# LED_Matrix_3_2.net
KiCad netlist of a schematic drawn in EAGLE
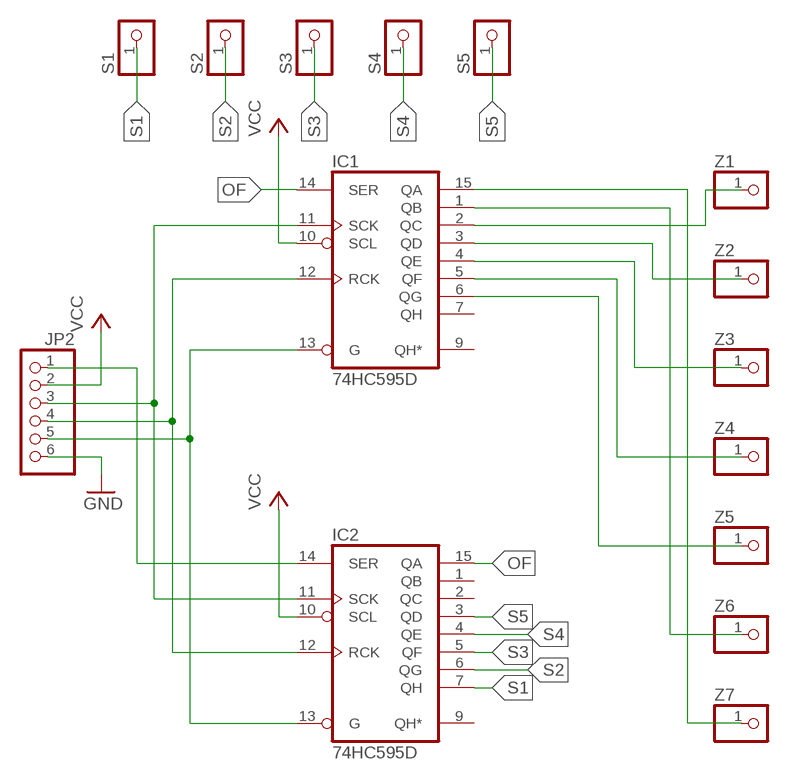
[diagram p0: schematic, sheet 1]

(export (version "E")
  (design (tool "Eeschema 10.0.6"))
  (components
    (comp (ref "IC1")
      (value "74HC595D")
      (footprint "eagle-import:SO16")
      (libsource (lib "eagle-import") (part "74595DHC"))
    )
    (comp (ref "IC2")
      (value "74HC595D")
      (footprint "eagle-import:SO16")
      (libsource (lib "eagle-import") (part "74595DHC"))
    )
    (comp (ref "JP2")
      (value "PINHD-1X6")
      (footprint "eagle-import:1X06")
      (libsource (lib "eagle-import") (part "PINHD-1X6"))
    )
    (comp (ref "S1")
      (value "PINHD-1X1")
      (footprint "eagle-import:1X01")
      (libsource (lib "eagle-import") (part "PINHD-1X1"))
    )
    (comp (ref "S2")
      (value "PINHD-1X1")
      (footprint "eagle-import:1X01")
      (libsource (lib "eagle-import") (part "PINHD-1X1"))
    )
    (comp (ref "S3")
      (value "PINHD-1X1")
      (footprint "eagle-import:1X01")
      (libsource (lib "eagle-import") (part "PINHD-1X1"))
    )
    (comp (ref "S4")
      (value "PINHD-1X1")
      (footprint "eagle-import:1X01")
      (libsource (lib "eagle-import") (part "PINHD-1X1"))
    )
    (comp (ref "S5")
      (value "PINHD-1X1")
      (footprint "eagle-import:1X01")
      (libsource (lib "eagle-import") (part "PINHD-1X1"))
    )
    (comp (ref "Z1")
      (value "PINHD-1X1")
      (footprint "eagle-import:1X01")
      (libsource (lib "eagle-import") (part "PINHD-1X1"))
    )
    (comp (ref "Z2")
      (value "PINHD-1X1")
      (footprint "eagle-import:1X01")
      (libsource (lib "eagle-import") (part "PINHD-1X1"))
    )
    (comp (ref "Z3")
      (value "PINHD-1X1")
      (footprint "eagle-import:1X01")
      (libsource (lib "eagle-import") (part "PINHD-1X1"))
    )
    (comp (ref "Z4")
      (value "PINHD-1X1")
      (footprint "eagle-import:1X01")
      (libsource (lib "eagle-import") (part "PINHD-1X1"))
    )
    (comp (ref "Z5")
      (value "PINHD-1X1")
      (footprint "eagle-import:1X01")
      (libsource (lib "eagle-import") (part "PINHD-1X1"))
    )
    (comp (ref "Z6")
      (value "PINHD-1X1")
      (footprint "eagle-import:1X01")
      (libsource (lib "eagle-import") (part "PINHD-1X1"))
    )
    (comp (ref "Z7")
      (value "PINHD-1X1")
      (footprint "eagle-import:1X01")
      (libsource (lib "eagle-import") (part "PINHD-1X1"))
    )
  )
  (nets
    (net (code "1") (name "GND") (class "Default")
      (node (ref "JP2") (pin "6") (pinfunction "6_6") (pintype "passive"))
    )
    (net (code "2") (name "Net-(IC1A-G)") (class "Default")
      (node (ref "IC1") (pin "13") (pinfunction "G_13") (pintype "input"))
      (node (ref "IC2") (pin "13") (pinfunction "G_13") (pintype "input"))
      (node (ref "JP2") (pin "5") (pinfunction "5_5") (pintype "passive"))
    )
    (net (code "3") (name "Net-(IC1A-QA)") (class "Default")
      (node (ref "IC1") (pin "15") (pinfunction "QA_15") (pintype "tri_state"))
      (node (ref "Z7") (pin "1") (pinfunction "1_1") (pintype "passive"))
    )
    (net (code "4") (name "Net-(IC1A-QB)") (class "Default")
      (node (ref "IC1") (pin "1") (pinfunction "QB_1") (pintype "tri_state"))
      (node (ref "Z6") (pin "1") (pinfunction "1_1") (pintype "passive"))
    )
    (net (code "5") (name "Net-(IC1A-QC)") (class "Default")
      (node (ref "IC1") (pin "2") (pinfunction "QC_2") (pintype "tri_state"))
      (node (ref "Z1") (pin "1") (pinfunction "1_1") (pintype "passive"))
    )
    (net (code "6") (name "Net-(IC1A-QD)") (class "Default")
      (node (ref "IC1") (pin "3") (pinfunction "QD_3") (pintype "tri_state"))
      (node (ref "Z2") (pin "1") (pinfunction "1_1") (pintype "passive"))
    )
    (net (code "7") (name "Net-(IC1A-QE)") (class "Default")
      (node (ref "IC1") (pin "4") (pinfunction "QE_4") (pintype "tri_state"))
      (node (ref "Z3") (pin "1") (pinfunction "1_1") (pintype "passive"))
    )
    (net (code "8") (name "Net-(IC1A-QF)") (class "Default")
      (node (ref "IC1") (pin "5") (pinfunction "QF_5") (pintype "tri_state"))
      (node (ref "Z4") (pin "1") (pinfunction "1_1") (pintype "passive"))
    )
    (net (code "9") (name "Net-(IC1A-QG)") (class "Default")
      (node (ref "IC1") (pin "6") (pinfunction "QG_6") (pintype "tri_state"))
      (node (ref "Z5") (pin "1") (pinfunction "1_1") (pintype "passive"))
    )
    (net (code "10") (name "Net-(IC1A-RCK)") (class "Default")
      (node (ref "IC1") (pin "12") (pinfunction "RCK_12") (pintype "input"))
      (node (ref "IC2") (pin "12") (pinfunction "RCK_12") (pintype "input"))
      (node (ref "JP2") (pin "4") (pinfunction "4_4") (pintype "passive"))
    )
    (net (code "11") (name "Net-(IC1A-SCK)") (class "Default")
      (node (ref "IC1") (pin "11") (pinfunction "SCK_11") (pintype "input"))
      (node (ref "IC2") (pin "11") (pinfunction "SCK_11") (pintype "input"))
      (node (ref "JP2") (pin "3") (pinfunction "3_3") (pintype "passive"))
    )
    (net (code "12") (name "Net-(IC2A-SER)") (class "Default")
      (node (ref "IC2") (pin "14") (pinfunction "SER_14") (pintype "input"))
      (node (ref "JP2") (pin "1") (pinfunction "1_1") (pintype "passive"))
    )
    (net (code "13") (name "OF") (class "Default")
      (node (ref "IC1") (pin "14") (pinfunction "SER_14") (pintype "input"))
      (node (ref "IC2") (pin "15") (pinfunction "QA_15") (pintype "tri_state"))
    )
    (net (code "14") (name "S1") (class "Default")
      (node (ref "IC2") (pin "7") (pinfunction "QH_7") (pintype "tri_state"))
      (node (ref "S1") (pin "1") (pinfunction "1_1") (pintype "passive"))
    )
    (net (code "15") (name "S2") (class "Default")
      (node (ref "IC2") (pin "6") (pinfunction "QG_6") (pintype "tri_state"))
      (node (ref "S2") (pin "1") (pinfunction "1_1") (pintype "passive"))
    )
    (net (code "16") (name "S3") (class "Default")
      (node (ref "IC2") (pin "5") (pinfunction "QF_5") (pintype "tri_state"))
      (node (ref "S3") (pin "1") (pinfunction "1_1") (pintype "passive"))
    )
    (net (code "17") (name "S4") (class "Default")
      (node (ref "IC2") (pin "4") (pinfunction "QE_4") (pintype "tri_state"))
      (node (ref "S4") (pin "1") (pinfunction "1_1") (pintype "passive"))
    )
    (net (code "18") (name "S5") (class "Default")
      (node (ref "IC2") (pin "3") (pinfunction "QD_3") (pintype "tri_state"))
      (node (ref "S5") (pin "1") (pinfunction "1_1") (pintype "passive"))
    )
    (net (code "19") (name "VCC") (class "Default")
      (node (ref "IC1") (pin "10") (pinfunction "SCL_10") (pintype "input"))
      (node (ref "IC2") (pin "10") (pinfunction "SCL_10") (pintype "input"))
      (node (ref "JP2") (pin "2") (pinfunction "2_2") (pintype "passive"))
    )
    (net (code "20") (name "unconnected-(IC1A-QH*-Pad9)") (class "Default")
      (node (ref "IC1") (pin "9") (pinfunction "QH*_9") (pintype "tri_state"))
    )
    (net (code "21") (name "unconnected-(IC1A-QH-Pad7)") (class "Default")
      (node (ref "IC1") (pin "7") (pinfunction "QH_7") (pintype "tri_state"))
    )
    (net (code "22") (name "unconnected-(IC2A-QB-Pad1)") (class "Default")
      (node (ref "IC2") (pin "1") (pinfunction "QB_1") (pintype "tri_state"))
    )
    (net (code "23") (name "unconnected-(IC2A-QC-Pad2)") (class "Default")
      (node (ref "IC2") (pin "2") (pinfunction "QC_2") (pintype "tri_state"))
    )
    (net (code "24") (name "unconnected-(IC2A-QH*-Pad9)") (class "Default")
      (node (ref "IC2") (pin "9") (pinfunction "QH*_9") (pintype "tri_state"))
    )
  )
)
